# rimocon.net
KiCad netlist of a schematic drawn in EAGLE
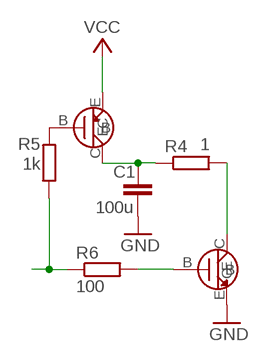
[diagram p0: schematic, sheet 1]

(export (version "E")
  (design (tool "Eeschema 10.0.6"))
  (components
    (comp (ref "C1")
      (value "100u")
      (footprint "eagle-import:C025-025X050")
      (libsource (lib "eagle-import") (part "C-EU025-025X050"))
    )
    (comp (ref "R4")
      (value "1")
      (footprint "eagle-import:0204_5")
      (libsource (lib "eagle-import") (part "R-EU_0204/5"))
    )
    (comp (ref "R5")
      (value "1k")
      (footprint "eagle-import:0204_5")
      (libsource (lib "eagle-import") (part "R-EU_0204/5"))
    )
    (comp (ref "R6")
      (value "100")
      (footprint "eagle-import:0204_5")
      (libsource (lib "eagle-import") (part "R-EU_0204/5"))
    )
    (comp (ref "U$1")
      (value "2SC1815")
      (footprint "eagle-import:1815")
      (libsource (lib "eagle-import") (part "2SC1815"))
    )
    (comp (ref "U$2")
      (value "2SA1815")
      (footprint "eagle-import:1815")
      (libsource (lib "eagle-import") (part "2SA1815"))
    )
  )
  (nets
    (net (code "1") (name "GND") (class "Default")
      (node (ref "C1") (pin "2") (pinfunction "2_2") (pintype "passive"))
      (node (ref "U$1") (pin "E") (pinfunction "E_E") (pintype "bidirectional"))
    )
    (net (code "2") (name "Net-(C1-Pad1)") (class "Default")
      (node (ref "C1") (pin "1") (pinfunction "1_1") (pintype "passive"))
      (node (ref "R4") (pin "1") (pinfunction "1_1") (pintype "passive"))
      (node (ref "U$2") (pin "C") (pinfunction "C_C") (pintype "bidirectional"))
    )
    (net (code "3") (name "Net-(R4-Pad2)") (class "Default")
      (node (ref "R4") (pin "2") (pinfunction "2_2") (pintype "passive"))
      (node (ref "U$1") (pin "C") (pinfunction "C_C") (pintype "bidirectional"))
    )
    (net (code "4") (name "Net-(R5-Pad1)") (class "Default")
      (node (ref "R5") (pin "1") (pinfunction "1_1") (pintype "passive"))
      (node (ref "R6") (pin "1") (pinfunction "1_1") (pintype "passive"))
    )
    (net (code "5") (name "Net-(R5-Pad2)") (class "Default")
      (node (ref "R5") (pin "2") (pinfunction "2_2") (pintype "passive"))
      (node (ref "U$2") (pin "B") (pinfunction "B_B") (pintype "bidirectional"))
    )
    (net (code "6") (name "Net-(R6-Pad2)") (class "Default")
      (node (ref "R6") (pin "2") (pinfunction "2_2") (pintype "passive"))
      (node (ref "U$1") (pin "B") (pinfunction "B_B") (pintype "bidirectional"))
    )
    (net (code "7") (name "VCC") (class "Default")
      (node (ref "U$2") (pin "E") (pinfunction "E_E") (pintype "bidirectional"))
    )
  )
)
